# My_Project_2023-03-21.net
KiCad netlist of a schematic drawn in EasyEDA Pro
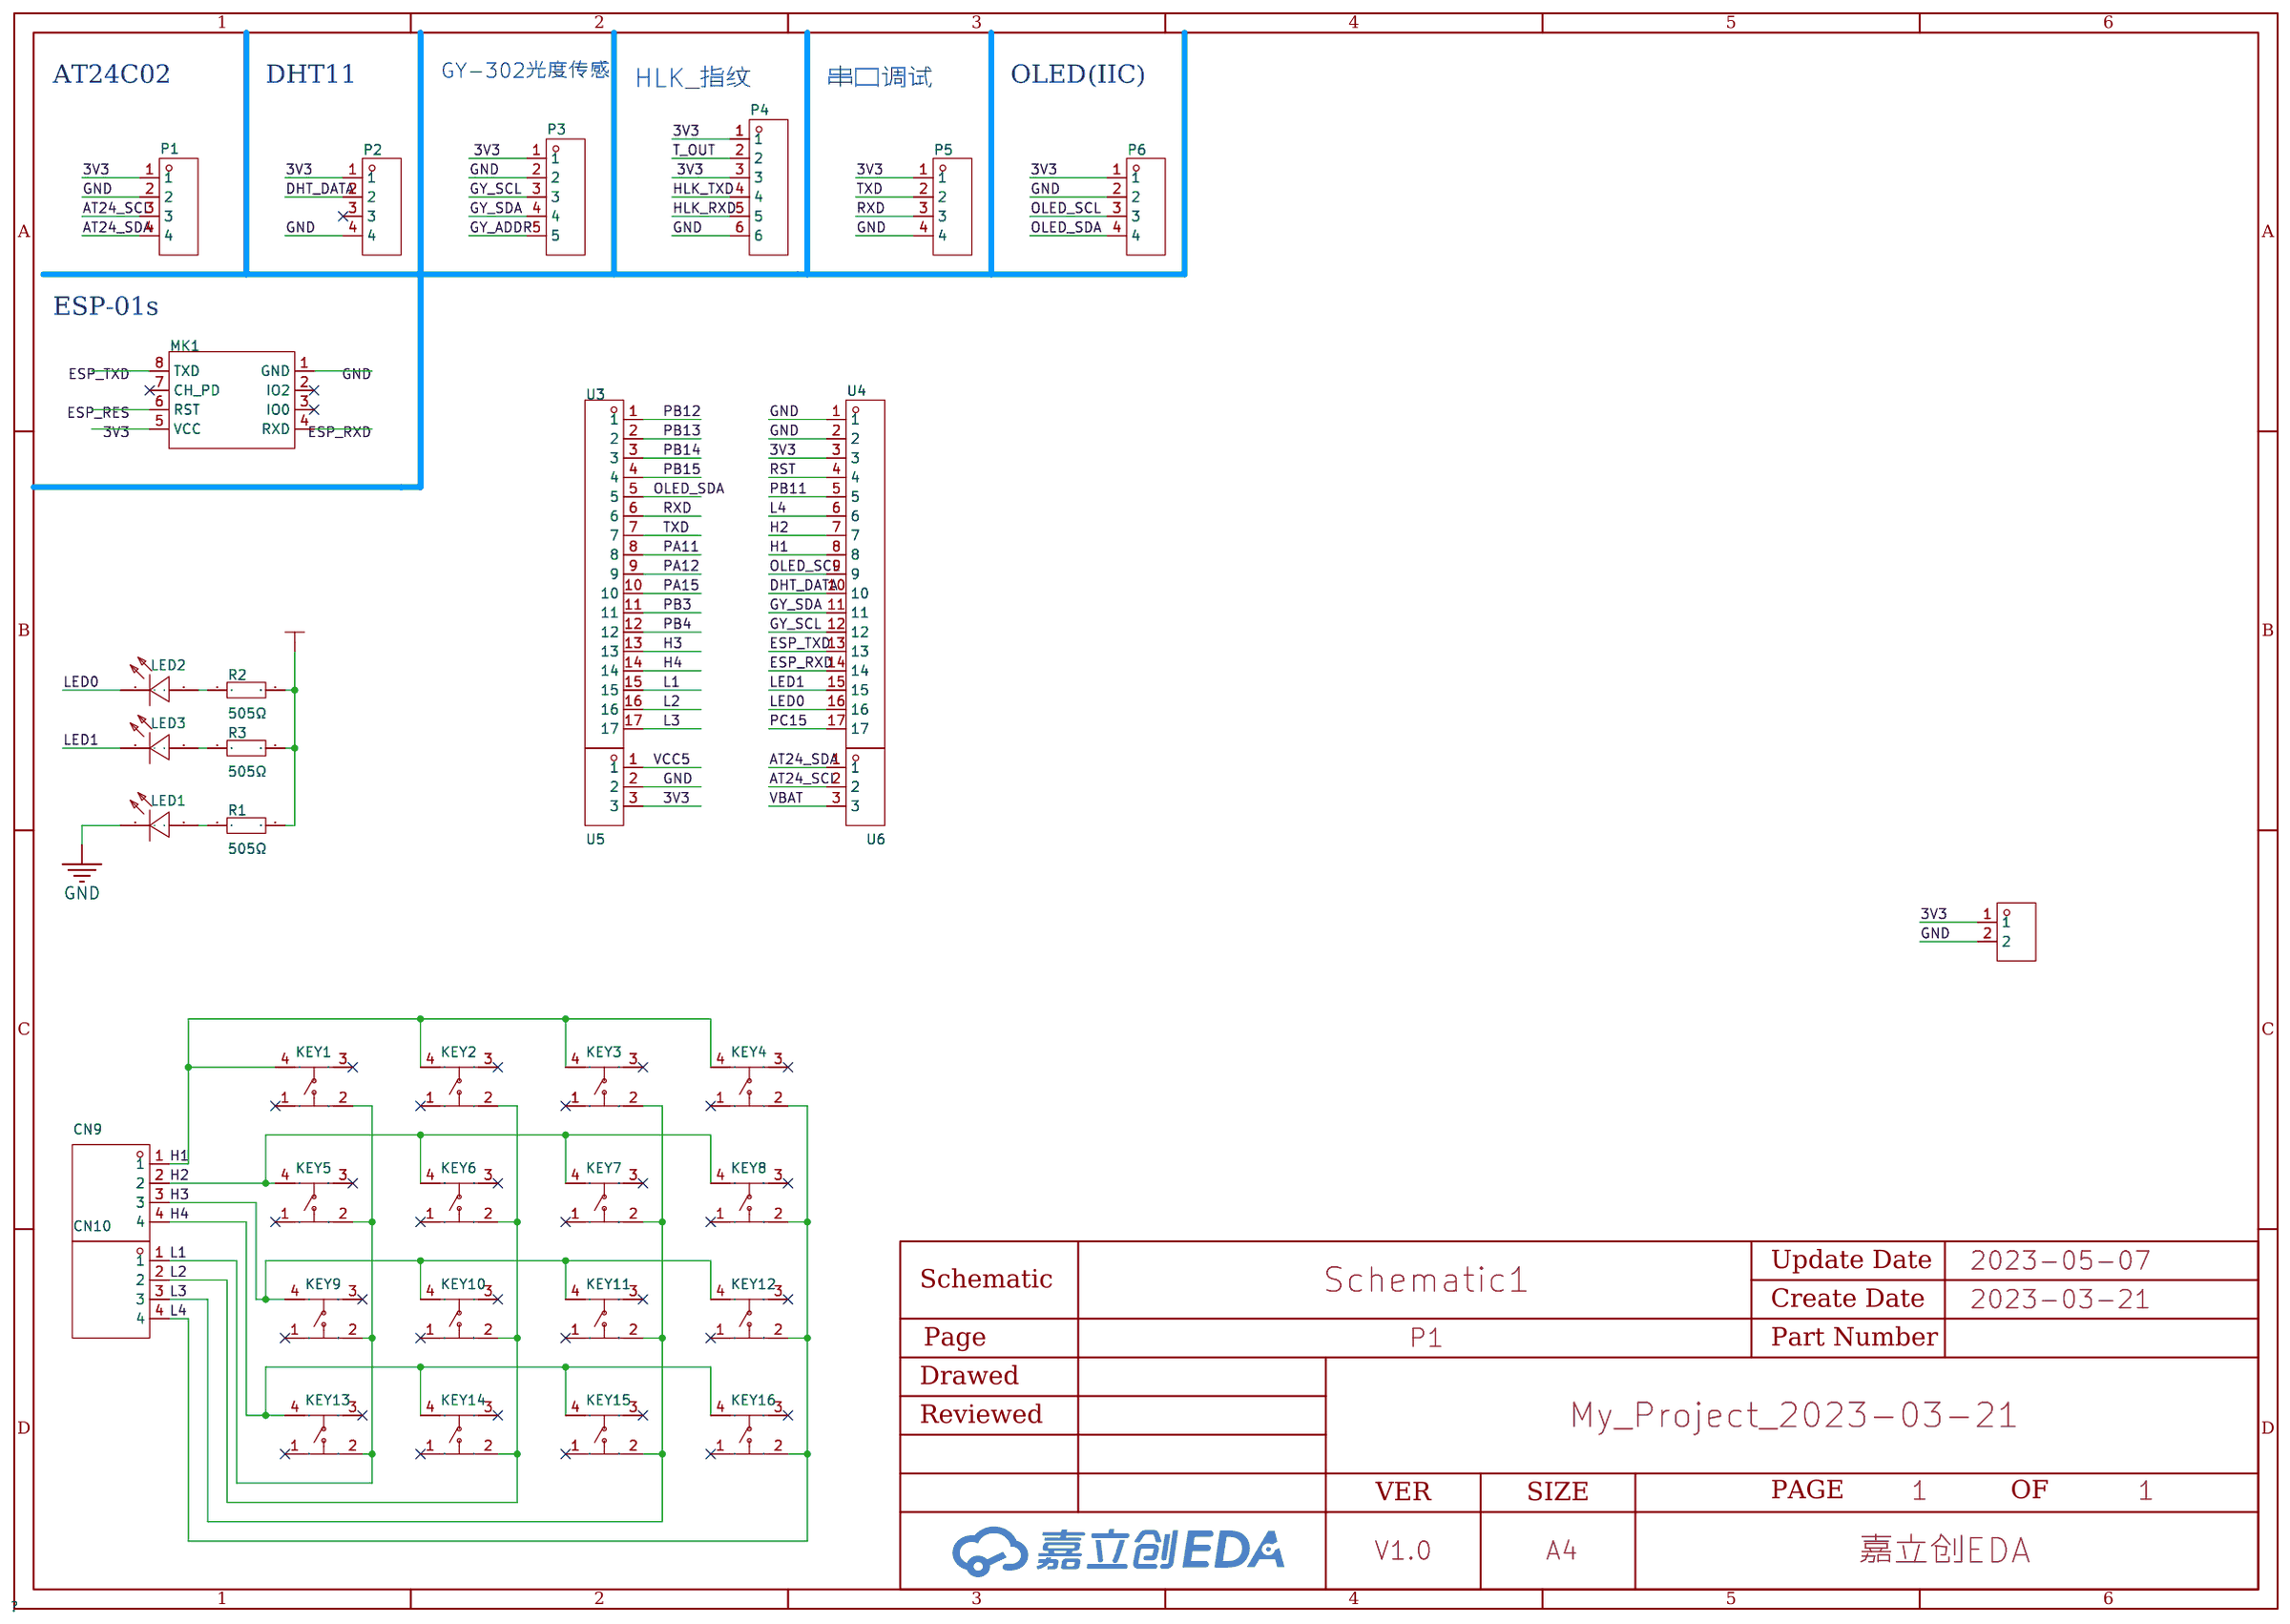
[diagram p0: schematic sheet]

(export (version "E")
  (design (tool "Eeschema 10.0.6"))
  (components
    (comp (ref "CN9")
      (value "RE-H042TD-1190(LF)(SN)")
      (footprint "easyedapro:HDR-TH_4P-P2.54-V_RE-H042TD-1190")
      (fields (field (name "Manufacturer") "JST"))
      (libsource (lib "easyedapro") (part "RE-H042TD-1190 (LF)(SN)"))
    )
    (comp (ref "CN10")
      (value "RE-H042TD-1190(LF)(SN)")
      (footprint "easyedapro:HDR-TH_4P-P2.54-V_RE-H042TD-1190")
      (fields (field (name "Manufacturer") "JST"))
      (libsource (lib "easyedapro") (part "RE-H042TD-1190 (LF)(SN)"))
    )
    (comp (ref "KEY1")
      (value "TL1105AF160Q")
      (footprint "easyedapro:KEY-TH_4P-L6.0-W6.0-P4.50-LS7.5")
      (description "触点电流:50mA;额定电压(DC):12V;电路结构:单刀单掷;安装方式:直插;按钮形状:圆形按钮;带灯:-;开关长度:6mm;开关宽度:6mm;开关高度:1.4mm;")
      (fields (field (name "Manufacturer") "E-Switch"))
      (libsource (lib "easyedapro") (part "TL1105AF160Q"))
    )
    (comp (ref "KEY2")
      (value "TL1105AF160Q")
      (footprint "easyedapro:KEY-TH_4P-L6.0-W6.0-P4.50-LS7.5")
      (description "触点电流:50mA;额定电压(DC):12V;电路结构:单刀单掷;安装方式:直插;按钮形状:圆形按钮;带灯:-;开关长度:6mm;开关宽度:6mm;开关高度:1.4mm;")
      (fields (field (name "Manufacturer") "E-Switch"))
      (libsource (lib "easyedapro") (part "TL1105AF160Q"))
    )
    (comp (ref "KEY3")
      (value "TL1105AF160Q")
      (footprint "easyedapro:KEY-TH_4P-L6.0-W6.0-P4.50-LS7.5")
      (description "触点电流:50mA;额定电压(DC):12V;电路结构:单刀单掷;安装方式:直插;按钮形状:圆形按钮;带灯:-;开关长度:6mm;开关宽度:6mm;开关高度:1.4mm;")
      (fields (field (name "Manufacturer") "E-Switch"))
      (libsource (lib "easyedapro") (part "TL1105AF160Q"))
    )
    (comp (ref "KEY4")
      (value "TL1105AF160Q")
      (footprint "easyedapro:KEY-TH_4P-L6.0-W6.0-P4.50-LS7.5")
      (description "触点电流:50mA;额定电压(DC):12V;电路结构:单刀单掷;安装方式:直插;按钮形状:圆形按钮;带灯:-;开关长度:6mm;开关宽度:6mm;开关高度:1.4mm;")
      (fields (field (name "Manufacturer") "E-Switch"))
      (libsource (lib "easyedapro") (part "TL1105AF160Q"))
    )
    (comp (ref "KEY5")
      (value "TL1105AF160Q")
      (footprint "easyedapro:KEY-TH_4P-L6.0-W6.0-P4.50-LS7.5")
      (description "触点电流:50mA;额定电压(DC):12V;电路结构:单刀单掷;安装方式:直插;按钮形状:圆形按钮;带灯:-;开关长度:6mm;开关宽度:6mm;开关高度:1.4mm;")
      (fields (field (name "Manufacturer") "E-Switch"))
      (libsource (lib "easyedapro") (part "TL1105AF160Q"))
    )
    (comp (ref "KEY6")
      (value "TL1105AF160Q")
      (footprint "easyedapro:KEY-TH_4P-L6.0-W6.0-P4.50-LS7.5")
      (description "触点电流:50mA;额定电压(DC):12V;电路结构:单刀单掷;安装方式:直插;按钮形状:圆形按钮;带灯:-;开关长度:6mm;开关宽度:6mm;开关高度:1.4mm;")
      (fields (field (name "Manufacturer") "E-Switch"))
      (libsource (lib "easyedapro") (part "TL1105AF160Q"))
    )
    (comp (ref "KEY7")
      (value "TL1105AF160Q")
      (footprint "easyedapro:KEY-TH_4P-L6.0-W6.0-P4.50-LS7.5")
      (description "触点电流:50mA;额定电压(DC):12V;电路结构:单刀单掷;安装方式:直插;按钮形状:圆形按钮;带灯:-;开关长度:6mm;开关宽度:6mm;开关高度:1.4mm;")
      (fields (field (name "Manufacturer") "E-Switch"))
      (libsource (lib "easyedapro") (part "TL1105AF160Q"))
    )
    (comp (ref "KEY8")
      (value "TL1105AF160Q")
      (footprint "easyedapro:KEY-TH_4P-L6.0-W6.0-P4.50-LS7.5")
      (description "触点电流:50mA;额定电压(DC):12V;电路结构:单刀单掷;安装方式:直插;按钮形状:圆形按钮;带灯:-;开关长度:6mm;开关宽度:6mm;开关高度:1.4mm;")
      (fields (field (name "Manufacturer") "E-Switch"))
      (libsource (lib "easyedapro") (part "TL1105AF160Q"))
    )
    (comp (ref "KEY9")
      (value "TL1105AF160Q")
      (footprint "easyedapro:KEY-TH_4P-L6.0-W6.0-P4.50-LS7.5")
      (description "触点电流:50mA;额定电压(DC):12V;电路结构:单刀单掷;安装方式:直插;按钮形状:圆形按钮;带灯:-;开关长度:6mm;开关宽度:6mm;开关高度:1.4mm;")
      (fields (field (name "Manufacturer") "E-Switch"))
      (libsource (lib "easyedapro") (part "TL1105AF160Q"))
    )
    (comp (ref "KEY10")
      (value "TL1105AF160Q")
      (footprint "easyedapro:KEY-TH_4P-L6.0-W6.0-P4.50-LS7.5")
      (description "触点电流:50mA;额定电压(DC):12V;电路结构:单刀单掷;安装方式:直插;按钮形状:圆形按钮;带灯:-;开关长度:6mm;开关宽度:6mm;开关高度:1.4mm;")
      (fields (field (name "Manufacturer") "E-Switch"))
      (libsource (lib "easyedapro") (part "TL1105AF160Q"))
    )
    (comp (ref "KEY11")
      (value "TL1105AF160Q")
      (footprint "easyedapro:KEY-TH_4P-L6.0-W6.0-P4.50-LS7.5")
      (description "触点电流:50mA;额定电压(DC):12V;电路结构:单刀单掷;安装方式:直插;按钮形状:圆形按钮;带灯:-;开关长度:6mm;开关宽度:6mm;开关高度:1.4mm;")
      (fields (field (name "Manufacturer") "E-Switch"))
      (libsource (lib "easyedapro") (part "TL1105AF160Q"))
    )
    (comp (ref "KEY12")
      (value "TL1105AF160Q")
      (footprint "easyedapro:KEY-TH_4P-L6.0-W6.0-P4.50-LS7.5")
      (description "触点电流:50mA;额定电压(DC):12V;电路结构:单刀单掷;安装方式:直插;按钮形状:圆形按钮;带灯:-;开关长度:6mm;开关宽度:6mm;开关高度:1.4mm;")
      (fields (field (name "Manufacturer") "E-Switch"))
      (libsource (lib "easyedapro") (part "TL1105AF160Q"))
    )
    (comp (ref "KEY13")
      (value "TL1105AF160Q")
      (footprint "easyedapro:KEY-TH_4P-L6.0-W6.0-P4.50-LS7.5")
      (description "触点电流:50mA;额定电压(DC):12V;电路结构:单刀单掷;安装方式:直插;按钮形状:圆形按钮;带灯:-;开关长度:6mm;开关宽度:6mm;开关高度:1.4mm;")
      (fields (field (name "Manufacturer") "E-Switch"))
      (libsource (lib "easyedapro") (part "TL1105AF160Q"))
    )
    (comp (ref "KEY14")
      (value "TL1105AF160Q")
      (footprint "easyedapro:KEY-TH_4P-L6.0-W6.0-P4.50-LS7.5")
      (description "触点电流:50mA;额定电压(DC):12V;电路结构:单刀单掷;安装方式:直插;按钮形状:圆形按钮;带灯:-;开关长度:6mm;开关宽度:6mm;开关高度:1.4mm;")
      (fields (field (name "Manufacturer") "E-Switch"))
      (libsource (lib "easyedapro") (part "TL1105AF160Q"))
    )
    (comp (ref "KEY15")
      (value "TL1105AF160Q")
      (footprint "easyedapro:KEY-TH_4P-L6.0-W6.0-P4.50-LS7.5")
      (description "触点电流:50mA;额定电压(DC):12V;电路结构:单刀单掷;安装方式:直插;按钮形状:圆形按钮;带灯:-;开关长度:6mm;开关宽度:6mm;开关高度:1.4mm;")
      (fields (field (name "Manufacturer") "E-Switch"))
      (libsource (lib "easyedapro") (part "TL1105AF160Q"))
    )
    (comp (ref "KEY16")
      (value "TL1105AF160Q")
      (footprint "easyedapro:KEY-TH_4P-L6.0-W6.0-P4.50-LS7.5")
      (description "触点电流:50mA;额定电压(DC):12V;电路结构:单刀单掷;安装方式:直插;按钮形状:圆形按钮;带灯:-;开关长度:6mm;开关宽度:6mm;开关高度:1.4mm;")
      (fields (field (name "Manufacturer") "E-Switch"))
      (libsource (lib "easyedapro") (part "TL1105AF160Q"))
    )
    (comp (ref "LED1")
      (value "NCD0805R1")
      (footprint "easyedapro:LED0805-RD_RED")
      (description "发光颜色:红灯;")
      (fields (field (name "Manufacturer") "国星光电"))
      (libsource (lib "easyedapro") (part "FC-2012HRK-620D"))
    )
    (comp (ref "LED2")
      (value "NCD0805R1")
      (footprint "easyedapro:LED0805-RD_RED")
      (description "发光颜色:红灯;")
      (fields (field (name "Manufacturer") "国星光电"))
      (libsource (lib "easyedapro") (part "FC-2012HRK-620D"))
    )
    (comp (ref "LED3")
      (value "NCD0805R1")
      (footprint "easyedapro:LED0805-RD_RED")
      (description "发光颜色:红灯;")
      (fields (field (name "Manufacturer") "国星光电"))
      (libsource (lib "easyedapro") (part "FC-2012HRK-620D"))
    )
    (comp (ref "MK1")
      (value "ESP-01S")
      (footprint "easyedapro:WIRELM-TH_ESP-01S")
      (description "PCB天线、DIP接口、方便DIY的ESP8266EX WIFI模块")
      (libsource (lib "easyedapro") (part "ESP-01S_C82893"))
    )
    (comp (ref "P1")
      (value "CON4")
      (footprint "easyedapro:CONN-TH_4P-P2.50-XH2.54-4P")
      (libsource (lib "easyedapro") (part "CON4"))
    )
    (comp (ref "P2")
      (value "CON4")
      (footprint "easyedapro:CONN-TH_4P-P2.50-XH2.54-4P")
      (libsource (lib "easyedapro") (part "CON4"))
    )
    (comp (ref "P3")
      (value "XH5/2.54mm/180")
      (footprint "easyedapro:CONN-TH_5P-P2.54_C9900008095")
      (libsource (lib "easyedapro") (part "XH5/2.54MM/180"))
    )
    (comp (ref "P4")
      (value "PH6_ZZ_2MM54")
      (footprint "easyedapro:CONN-TH_6P-P2.54_PH6_ZZ_2MM54")
      (libsource (lib "easyedapro") (part "PH6_ZZ_2MM54"))
    )
    (comp (ref "P5")
      (value "CON4")
      (footprint "easyedapro:CONN-TH_4P-P2.50-XH2.54-4P")
      (libsource (lib "easyedapro") (part "CON4"))
    )
    (comp (ref "P6")
      (value "CON4")
      (footprint "easyedapro:CONN-TH_4P-P2.50-XH2.54-4P")
      (libsource (lib "easyedapro") (part "CON4"))
    )
    (comp (ref "R1")
      (value "505Ω")
      (footprint "easyedapro:R0805")
      (description "电阻类型:金属膜电阻;阻值:505Ω;精度:±0.1%;功率:125mW;")
      (fields (field (name "Manufacturer Part") "RN73H2ATTD5050B10") (field (name "Manufacturer") "KOA"))
      (libsource (lib "easyedapro") (part "RN73H2ATTD5050B10"))
    )
    (comp (ref "R2")
      (value "505Ω")
      (footprint "easyedapro:R0805")
      (description "电阻类型:金属膜电阻;阻值:505Ω;精度:±0.1%;功率:125mW;")
      (fields (field (name "Manufacturer Part") "RN73H2ATTD5050B10") (field (name "Manufacturer") "KOA"))
      (libsource (lib "easyedapro") (part "RN73H2ATTD5050B10"))
    )
    (comp (ref "R3")
      (value "505Ω")
      (footprint "easyedapro:R0805")
      (description "电阻类型:金属膜电阻;阻值:505Ω;精度:±0.1%;功率:125mW;")
      (fields (field (name "Manufacturer Part") "RN73H2ATTD5050B10") (field (name "Manufacturer") "KOA"))
      (libsource (lib "easyedapro") (part "RN73H2ATTD5050B10"))
    )
    (comp (ref "U3") (value "~") (footprint "easyedapro:CON18") (libsource (lib "easyedapro") (part "CON18")))
    (comp (ref "U4") (value "~") (footprint "easyedapro:CON18") (libsource (lib "easyedapro") (part "CON18")))
    (comp (ref "U5")
      (value "XH2.54-3")
      (footprint "easyedapro:CONN-TH_3P-P2.54_XH2.54-3")
      (libsource (lib "easyedapro") (part "XH2.54-3"))
    )
    (comp (ref "U6")
      (value "XH2.54-3")
      (footprint "easyedapro:CONN-TH_3P-P2.54_XH2.54-3")
      (libsource (lib "easyedapro") (part "XH2.54-3"))
    )
    (comp (ref "U8")
      (value "DB302-5.0-2P-GN-S")
      (footprint "easyedapro:CONN-TH_DB302-5.0-2P")
      (fields (field (name "Manufacturer") "DIBO(地博电气)"))
      (libsource (lib "easyedapro") (part "DB302-5.0-2P-GN-S"))
    )
  )
  (nets
    (net (code "1") (name "/AT24_SCL") (class "Default")
      (node (ref "P1") (pin "3") (pinfunction "3_3") (pintype "input"))
      (node (ref "U6") (pin "2") (pinfunction "2_2") (pintype "input"))
    )
    (net (code "2") (name "/AT24_SDA") (class "Default")
      (node (ref "P1") (pin "4") (pinfunction "4_4") (pintype "input"))
      (node (ref "U6") (pin "1") (pinfunction "1_1") (pintype "input"))
    )
    (net (code "3") (name "/DHT_DATA") (class "Default")
      (node (ref "P2") (pin "2") (pinfunction "2_2") (pintype "input"))
      (node (ref "U4") (pin "10") (pinfunction "10_10") (pintype "input"))
    )
    (net (code "4") (name "/ESP_RES") (class "Default")
      (node (ref "MK1") (pin "6") (pinfunction "RST_6") (pintype "input"))
    )
    (net (code "5") (name "/ESP_RXD") (class "Default")
      (node (ref "MK1") (pin "4") (pinfunction "RXD_4") (pintype "input"))
      (node (ref "U4") (pin "14") (pinfunction "14_14") (pintype "input"))
    )
    (net (code "6") (name "/ESP_TXD") (class "Default")
      (node (ref "MK1") (pin "8") (pinfunction "TXD_8") (pintype "input"))
      (node (ref "U4") (pin "13") (pinfunction "13_13") (pintype "input"))
    )
    (net (code "7") (name "/GY_ADDR") (class "Default")
      (node (ref "P3") (pin "5") (pinfunction "5_5") (pintype "input"))
    )
    (net (code "8") (name "/GY_SCL") (class "Default")
      (node (ref "P3") (pin "3") (pinfunction "3_3") (pintype "input"))
      (node (ref "U4") (pin "12") (pinfunction "12_12") (pintype "input"))
    )
    (net (code "9") (name "/GY_SDA") (class "Default")
      (node (ref "P3") (pin "4") (pinfunction "4_4") (pintype "input"))
      (node (ref "U4") (pin "11") (pinfunction "11_11") (pintype "input"))
    )
    (net (code "10") (name "/H1") (class "Default")
      (node (ref "CN9") (pin "1") (pinfunction "1_1") (pintype "input"))
      (node (ref "KEY1") (pin "4") (pinfunction "4_4") (pintype "input"))
      (node (ref "KEY2") (pin "4") (pinfunction "4_4") (pintype "input"))
      (node (ref "KEY3") (pin "4") (pinfunction "4_4") (pintype "input"))
      (node (ref "KEY4") (pin "4") (pinfunction "4_4") (pintype "input"))
      (node (ref "U4") (pin "8") (pinfunction "8_8") (pintype "input"))
    )
    (net (code "11") (name "/H2") (class "Default")
      (node (ref "CN9") (pin "2") (pinfunction "2_2") (pintype "input"))
      (node (ref "KEY5") (pin "4") (pinfunction "4_4") (pintype "input"))
      (node (ref "KEY6") (pin "4") (pinfunction "4_4") (pintype "input"))
      (node (ref "KEY7") (pin "4") (pinfunction "4_4") (pintype "input"))
      (node (ref "KEY8") (pin "4") (pinfunction "4_4") (pintype "input"))
      (node (ref "U4") (pin "7") (pinfunction "7_7") (pintype "input"))
    )
    (net (code "12") (name "/H3") (class "Default")
      (node (ref "CN9") (pin "3") (pinfunction "3_3") (pintype "input"))
      (node (ref "KEY10") (pin "4") (pinfunction "4_4") (pintype "input"))
      (node (ref "KEY11") (pin "4") (pinfunction "4_4") (pintype "input"))
      (node (ref "KEY12") (pin "4") (pinfunction "4_4") (pintype "input"))
      (node (ref "KEY9") (pin "4") (pinfunction "4_4") (pintype "input"))
      (node (ref "U3") (pin "13") (pinfunction "13_13") (pintype "input"))
    )
    (net (code "13") (name "/H4") (class "Default")
      (node (ref "CN9") (pin "4") (pinfunction "4_4") (pintype "input"))
      (node (ref "KEY13") (pin "4") (pinfunction "4_4") (pintype "input"))
      (node (ref "KEY14") (pin "4") (pinfunction "4_4") (pintype "input"))
      (node (ref "KEY15") (pin "4") (pinfunction "4_4") (pintype "input"))
      (node (ref "KEY16") (pin "4") (pinfunction "4_4") (pintype "input"))
      (node (ref "U3") (pin "14") (pinfunction "14_14") (pintype "input"))
    )
    (net (code "14") (name "/HLK_RXD") (class "Default")
      (node (ref "P4") (pin "5") (pinfunction "5_5") (pintype "input"))
    )
    (net (code "15") (name "/HLK_TXD") (class "Default")
      (node (ref "P4") (pin "4") (pinfunction "4_4") (pintype "input"))
    )
    (net (code "16") (name "/L1") (class "Default")
      (node (ref "CN10") (pin "1") (pinfunction "1_1") (pintype "input"))
      (node (ref "KEY1") (pin "2") (pinfunction "2_2") (pintype "input"))
      (node (ref "KEY13") (pin "2") (pinfunction "2_2") (pintype "input"))
      (node (ref "KEY5") (pin "2") (pinfunction "2_2") (pintype "input"))
      (node (ref "KEY9") (pin "2") (pinfunction "2_2") (pintype "input"))
      (node (ref "U3") (pin "15") (pinfunction "15_15") (pintype "input"))
    )
    (net (code "17") (name "/L2") (class "Default")
      (node (ref "CN10") (pin "2") (pinfunction "2_2") (pintype "input"))
      (node (ref "KEY10") (pin "2") (pinfunction "2_2") (pintype "input"))
      (node (ref "KEY14") (pin "2") (pinfunction "2_2") (pintype "input"))
      (node (ref "KEY2") (pin "2") (pinfunction "2_2") (pintype "input"))
      (node (ref "KEY6") (pin "2") (pinfunction "2_2") (pintype "input"))
      (node (ref "U3") (pin "16") (pinfunction "16_16") (pintype "input"))
    )
    (net (code "18") (name "/L3") (class "Default")
      (node (ref "CN10") (pin "3") (pinfunction "3_3") (pintype "input"))
      (node (ref "KEY11") (pin "2") (pinfunction "2_2") (pintype "input"))
      (node (ref "KEY15") (pin "2") (pinfunction "2_2") (pintype "input"))
      (node (ref "KEY3") (pin "2") (pinfunction "2_2") (pintype "input"))
      (node (ref "KEY7") (pin "2") (pinfunction "2_2") (pintype "input"))
      (node (ref "U3") (pin "17") (pinfunction "17_17") (pintype "input"))
    )
    (net (code "19") (name "/L4") (class "Default")
      (node (ref "CN10") (pin "4") (pinfunction "4_4") (pintype "input"))
      (node (ref "KEY12") (pin "2") (pinfunction "2_2") (pintype "input"))
      (node (ref "KEY16") (pin "2") (pinfunction "2_2") (pintype "input"))
      (node (ref "KEY4") (pin "2") (pinfunction "2_2") (pintype "input"))
      (node (ref "KEY8") (pin "2") (pinfunction "2_2") (pintype "input"))
      (node (ref "U4") (pin "6") (pinfunction "6_6") (pintype "input"))
    )
    (net (code "20") (name "/LED0") (class "Default")
      (node (ref "LED2") (pin "1") (pinfunction "-_1") (pintype "input"))
      (node (ref "U4") (pin "16") (pinfunction "16_16") (pintype "input"))
    )
    (net (code "21") (name "/LED1") (class "Default")
      (node (ref "LED3") (pin "1") (pinfunction "-_1") (pintype "input"))
      (node (ref "U4") (pin "15") (pinfunction "15_15") (pintype "input"))
    )
    (net (code "22") (name "/OLED_SCL") (class "Default")
      (node (ref "P6") (pin "3") (pinfunction "3_3") (pintype "input"))
      (node (ref "U4") (pin "9") (pinfunction "9_9") (pintype "input"))
    )
    (net (code "23") (name "/OLED_SDA") (class "Default")
      (node (ref "P6") (pin "4") (pinfunction "4_4") (pintype "input"))
      (node (ref "U3") (pin "5") (pinfunction "5_5") (pintype "input"))
    )
    (net (code "24") (name "/PA11") (class "Default")
      (node (ref "U3") (pin "8") (pinfunction "8_8") (pintype "input"))
    )
    (net (code "25") (name "/PA12") (class "Default")
      (node (ref "U3") (pin "9") (pinfunction "9_9") (pintype "input"))
    )
    (net (code "26") (name "/PA15") (class "Default")
      (node (ref "U3") (pin "10") (pinfunction "10_10") (pintype "input"))
    )
    (net (code "27") (name "/PB3") (class "Default")
      (node (ref "U3") (pin "11") (pinfunction "11_11") (pintype "input"))
    )
    (net (code "28") (name "/PB4") (class "Default")
      (node (ref "U3") (pin "12") (pinfunction "12_12") (pintype "input"))
    )
    (net (code "29") (name "/PB11") (class "Default")
      (node (ref "U4") (pin "5") (pinfunction "5_5") (pintype "input"))
    )
    (net (code "30") (name "/PB12") (class "Default")
      (node (ref "U3") (pin "1") (pinfunction "1_1") (pintype "input"))
    )
    (net (code "31") (name "/PB13") (class "Default")
      (node (ref "U3") (pin "2") (pinfunction "2_2") (pintype "input"))
    )
    (net (code "32") (name "/PB14") (class "Default")
      (node (ref "U3") (pin "3") (pinfunction "3_3") (pintype "input"))
    )
    (net (code "33") (name "/PB15") (class "Default")
      (node (ref "U3") (pin "4") (pinfunction "4_4") (pintype "input"))
    )
    (net (code "34") (name "/PC15") (class "Default")
      (node (ref "U4") (pin "17") (pinfunction "17_17") (pintype "input"))
    )
    (net (code "35") (name "/RST") (class "Default")
      (node (ref "U4") (pin "4") (pinfunction "4_4") (pintype "input"))
    )
    (net (code "36") (name "/RXD") (class "Default")
      (node (ref "P5") (pin "3") (pinfunction "3_3") (pintype "input"))
      (node (ref "U3") (pin "6") (pinfunction "6_6") (pintype "input"))
    )
    (net (code "37") (name "/TXD") (class "Default")
      (node (ref "P5") (pin "2") (pinfunction "2_2") (pintype "input"))
      (node (ref "U3") (pin "7") (pinfunction "7_7") (pintype "input"))
    )
    (net (code "38") (name "/T_OUT") (class "Default")
      (node (ref "P4") (pin "2") (pinfunction "2_2") (pintype "input"))
    )
    (net (code "39") (name "/VBAT") (class "Default")
      (node (ref "U6") (pin "3") (pinfunction "3_3") (pintype "input"))
    )
    (net (code "40") (name "/VCC5") (class "Default")
      (node (ref "U5") (pin "1") (pinfunction "1_1") (pintype "input"))
    )
    (net (code "41") (name "3V3") (class "Default")
      (node (ref "MK1") (pin "5") (pinfunction "VCC_5") (pintype "input"))
      (node (ref "P1") (pin "1") (pinfunction "1_1") (pintype "input"))
      (node (ref "P2") (pin "1") (pinfunction "1_1") (pintype "input"))
      (node (ref "P3") (pin "1") (pinfunction "1_1") (pintype "input"))
      (node (ref "P4") (pin "1") (pinfunction "1_1") (pintype "input"))
      (node (ref "P4") (pin "3") (pinfunction "3_3") (pintype "input"))
      (node (ref "P5") (pin "1") (pinfunction "1_1") (pintype "input"))
      (node (ref "P6") (pin "1") (pinfunction "1_1") (pintype "input"))
      (node (ref "R1") (pin "2") (pinfunction "2_2") (pintype "input"))
      (node (ref "R2") (pin "2") (pinfunction "2_2") (pintype "input"))
      (node (ref "R3") (pin "2") (pinfunction "2_2") (pintype "input"))
      (node (ref "U4") (pin "3") (pinfunction "3_3") (pintype "input"))
      (node (ref "U5") (pin "3") (pinfunction "3_3") (pintype "input"))
      (node (ref "U8") (pin "1") (pinfunction "1_1") (pintype "input"))
    )
    (net (code "42") (name "GND") (class "Default")
      (node (ref "LED1") (pin "1") (pinfunction "-_1") (pintype "input"))
      (node (ref "MK1") (pin "1") (pinfunction "GND_1") (pintype "input"))
      (node (ref "P1") (pin "2") (pinfunction "2_2") (pintype "input"))
      (node (ref "P2") (pin "4") (pinfunction "4_4") (pintype "input"))
      (node (ref "P3") (pin "2") (pinfunction "2_2") (pintype "input"))
      (node (ref "P4") (pin "6") (pinfunction "6_6") (pintype "input"))
      (node (ref "P5") (pin "4") (pinfunction "4_4") (pintype "input"))
      (node (ref "P6") (pin "2") (pinfunction "2_2") (pintype "input"))
      (node (ref "U4") (pin "1") (pinfunction "1_1") (pintype "input"))
      (node (ref "U4") (pin "2") (pinfunction "2_2") (pintype "input"))
      (node (ref "U5") (pin "2") (pinfunction "2_2") (pintype "input"))
      (node (ref "U8") (pin "2") (pinfunction "2_2") (pintype "input"))
    )
    (net (code "43") (name "Net-(LED1-+)") (class "Default")
      (node (ref "LED1") (pin "2") (pinfunction "+_2") (pintype "input"))
      (node (ref "R1") (pin "1") (pinfunction "1_1") (pintype "input"))
    )
    (net (code "44") (name "Net-(LED2-+)") (class "Default")
      (node (ref "LED2") (pin "2") (pinfunction "+_2") (pintype "input"))
      (node (ref "R2") (pin "1") (pinfunction "1_1") (pintype "input"))
    )
    (net (code "45") (name "Net-(LED3-+)") (class "Default")
      (node (ref "LED3") (pin "2") (pinfunction "+_2") (pintype "input"))
      (node (ref "R3") (pin "1") (pinfunction "1_1") (pintype "input"))
    )
    (net (code "46") (name "unconnected-(KEY1-Pad1)") (class "Default")
      (node (ref "KEY1") (pin "1") (pinfunction "1_1") (pintype "input+no_connect"))
    )
    (net (code "47") (name "unconnected-(KEY1-Pad3)") (class "Default")
      (node (ref "KEY1") (pin "3") (pinfunction "3_3") (pintype "input+no_connect"))
    )
    (net (code "48") (name "unconnected-(KEY2-Pad1)") (class "Default")
      (node (ref "KEY2") (pin "1") (pinfunction "1_1") (pintype "input+no_connect"))
    )
    (net (code "49") (name "unconnected-(KEY2-Pad3)") (class "Default")
      (node (ref "KEY2") (pin "3") (pinfunction "3_3") (pintype "input+no_connect"))
    )
    (net (code "50") (name "unconnected-(KEY3-Pad1)") (class "Default")
      (node (ref "KEY3") (pin "1") (pinfunction "1_1") (pintype "input+no_connect"))
    )
    (net (code "51") (name "unconnected-(KEY3-Pad3)") (class "Default")
      (node (ref "KEY3") (pin "3") (pinfunction "3_3") (pintype "input+no_connect"))
    )
    (net (code "52") (name "unconnected-(KEY4-Pad1)") (class "Default")
      (node (ref "KEY4") (pin "1") (pinfunction "1_1") (pintype "input+no_connect"))
    )
    (net (code "53") (name "unconnected-(KEY4-Pad3)") (class "Default")
      (node (ref "KEY4") (pin "3") (pinfunction "3_3") (pintype "input+no_connect"))
    )
    (net (code "54") (name "unconnected-(KEY5-Pad1)") (class "Default")
      (node (ref "KEY5") (pin "1") (pinfunction "1_1") (pintype "input+no_connect"))
    )
    (net (code "55") (name "unconnected-(KEY5-Pad3)") (class "Default")
      (node (ref "KEY5") (pin "3") (pinfunction "3_3") (pintype "input+no_connect"))
    )
    (net (code "56") (name "unconnected-(KEY6-Pad1)") (class "Default")
      (node (ref "KEY6") (pin "1") (pinfunction "1_1") (pintype "input+no_connect"))
    )
    (net (code "57") (name "unconnected-(KEY6-Pad3)") (class "Default")
      (node (ref "KEY6") (pin "3") (pinfunction "3_3") (pintype "input+no_connect"))
    )
    (net (code "58") (name "unconnected-(KEY7-Pad1)") (class "Default")
      (node (ref "KEY7") (pin "1") (pinfunction "1_1") (pintype "input+no_connect"))
    )
    (net (code "59") (name "unconnected-(KEY7-Pad3)") (class "Default")
      (node (ref "KEY7") (pin "3") (pinfunction "3_3") (pintype "input+no_connect"))
    )
    (net (code "60") (name "unconnected-(KEY8-Pad1)") (class "Default")
      (node (ref "KEY8") (pin "1") (pinfunction "1_1") (pintype "input+no_connect"))
    )
    (net (code "61") (name "unconnected-(KEY8-Pad3)") (class "Default")
      (node (ref "KEY8") (pin "3") (pinfunction "3_3") (pintype "input+no_connect"))
    )
    (net (code "62") (name "unconnected-(KEY9-Pad1)") (class "Default")
      (node (ref "KEY9") (pin "1") (pinfunction "1_1") (pintype "input+no_connect"))
    )
    (net (code "63") (name "unconnected-(KEY9-Pad3)") (class "Default")
      (node (ref "KEY9") (pin "3") (pinfunction "3_3") (pintype "input+no_connect"))
    )
    (net (code "64") (name "unconnected-(KEY10-Pad1)") (class "Default")
      (node (ref "KEY10") (pin "1") (pinfunction "1_1") (pintype "input+no_connect"))
    )
    (net (code "65") (name "unconnected-(KEY10-Pad3)") (class "Default")
      (node (ref "KEY10") (pin "3") (pinfunction "3_3") (pintype "input+no_connect"))
    )
    (net (code "66") (name "unconnected-(KEY11-Pad1)") (class "Default")
      (node (ref "KEY11") (pin "1") (pinfunction "1_1") (pintype "input+no_connect"))
    )
    (net (code "67") (name "unconnected-(KEY11-Pad3)") (class "Default")
      (node (ref "KEY11") (pin "3") (pinfunction "3_3") (pintype "input+no_connect"))
    )
    (net (code "68") (name "unconnected-(KEY12-Pad1)") (class "Default")
      (node (ref "KEY12") (pin "1") (pinfunction "1_1") (pintype "input+no_connect"))
    )
    (net (code "69") (name "unconnected-(KEY12-Pad3)") (class "Default")
      (node (ref "KEY12") (pin "3") (pinfunction "3_3") (pintype "input+no_connect"))
    )
    (net (code "70") (name "unconnected-(KEY13-Pad1)") (class "Default")
      (node (ref "KEY13") (pin "1") (pinfunction "1_1") (pintype "input+no_connect"))
    )
    (net (code "71") (name "unconnected-(KEY13-Pad3)") (class "Default")
      (node (ref "KEY13") (pin "3") (pinfunction "3_3") (pintype "input+no_connect"))
    )
    (net (code "72") (name "unconnected-(KEY14-Pad1)") (class "Default")
      (node (ref "KEY14") (pin "1") (pinfunction "1_1") (pintype "input+no_connect"))
    )
    (net (code "73") (name "unconnected-(KEY14-Pad3)") (class "Default")
      (node (ref "KEY14") (pin "3") (pinfunction "3_3") (pintype "input+no_connect"))
    )
    (net (code "74") (name "unconnected-(KEY15-Pad1)") (class "Default")
      (node (ref "KEY15") (pin "1") (pinfunction "1_1") (pintype "input+no_connect"))
    )
    (net (code "75") (name "unconnected-(KEY15-Pad3)") (class "Default")
      (node (ref "KEY15") (pin "3") (pinfunction "3_3") (pintype "input+no_connect"))
    )
    (net (code "76") (name "unconnected-(KEY16-Pad1)") (class "Default")
      (node (ref "KEY16") (pin "1") (pinfunction "1_1") (pintype "input+no_connect"))
    )
    (net (code "77") (name "unconnected-(KEY16-Pad3)") (class "Default")
      (node (ref "KEY16") (pin "3") (pinfunction "3_3") (pintype "input+no_connect"))
    )
    (net (code "78") (name "unconnected-(MK1-CH_PD-Pad7)") (class "Default")
      (node (ref "MK1") (pin "7") (pinfunction "CH_PD_7") (pintype "input+no_connect"))
    )
    (net (code "79") (name "unconnected-(MK1-IO0-Pad3)") (class "Default")
      (node (ref "MK1") (pin "3") (pinfunction "IO0_3") (pintype "input+no_connect"))
    )
    (net (code "80") (name "unconnected-(MK1-IO2-Pad2)") (class "Default")
      (node (ref "MK1") (pin "2") (pinfunction "IO2_2") (pintype "input+no_connect"))
    )
    (net (code "81") (name "unconnected-(P2-Pad3)") (class "Default")
      (node (ref "P2") (pin "3") (pinfunction "3_3") (pintype "input+no_connect"))
    )
  )
)
